# SmartMatrixShield_V1.net
KiCad netlist of a schematic drawn in EAGLE
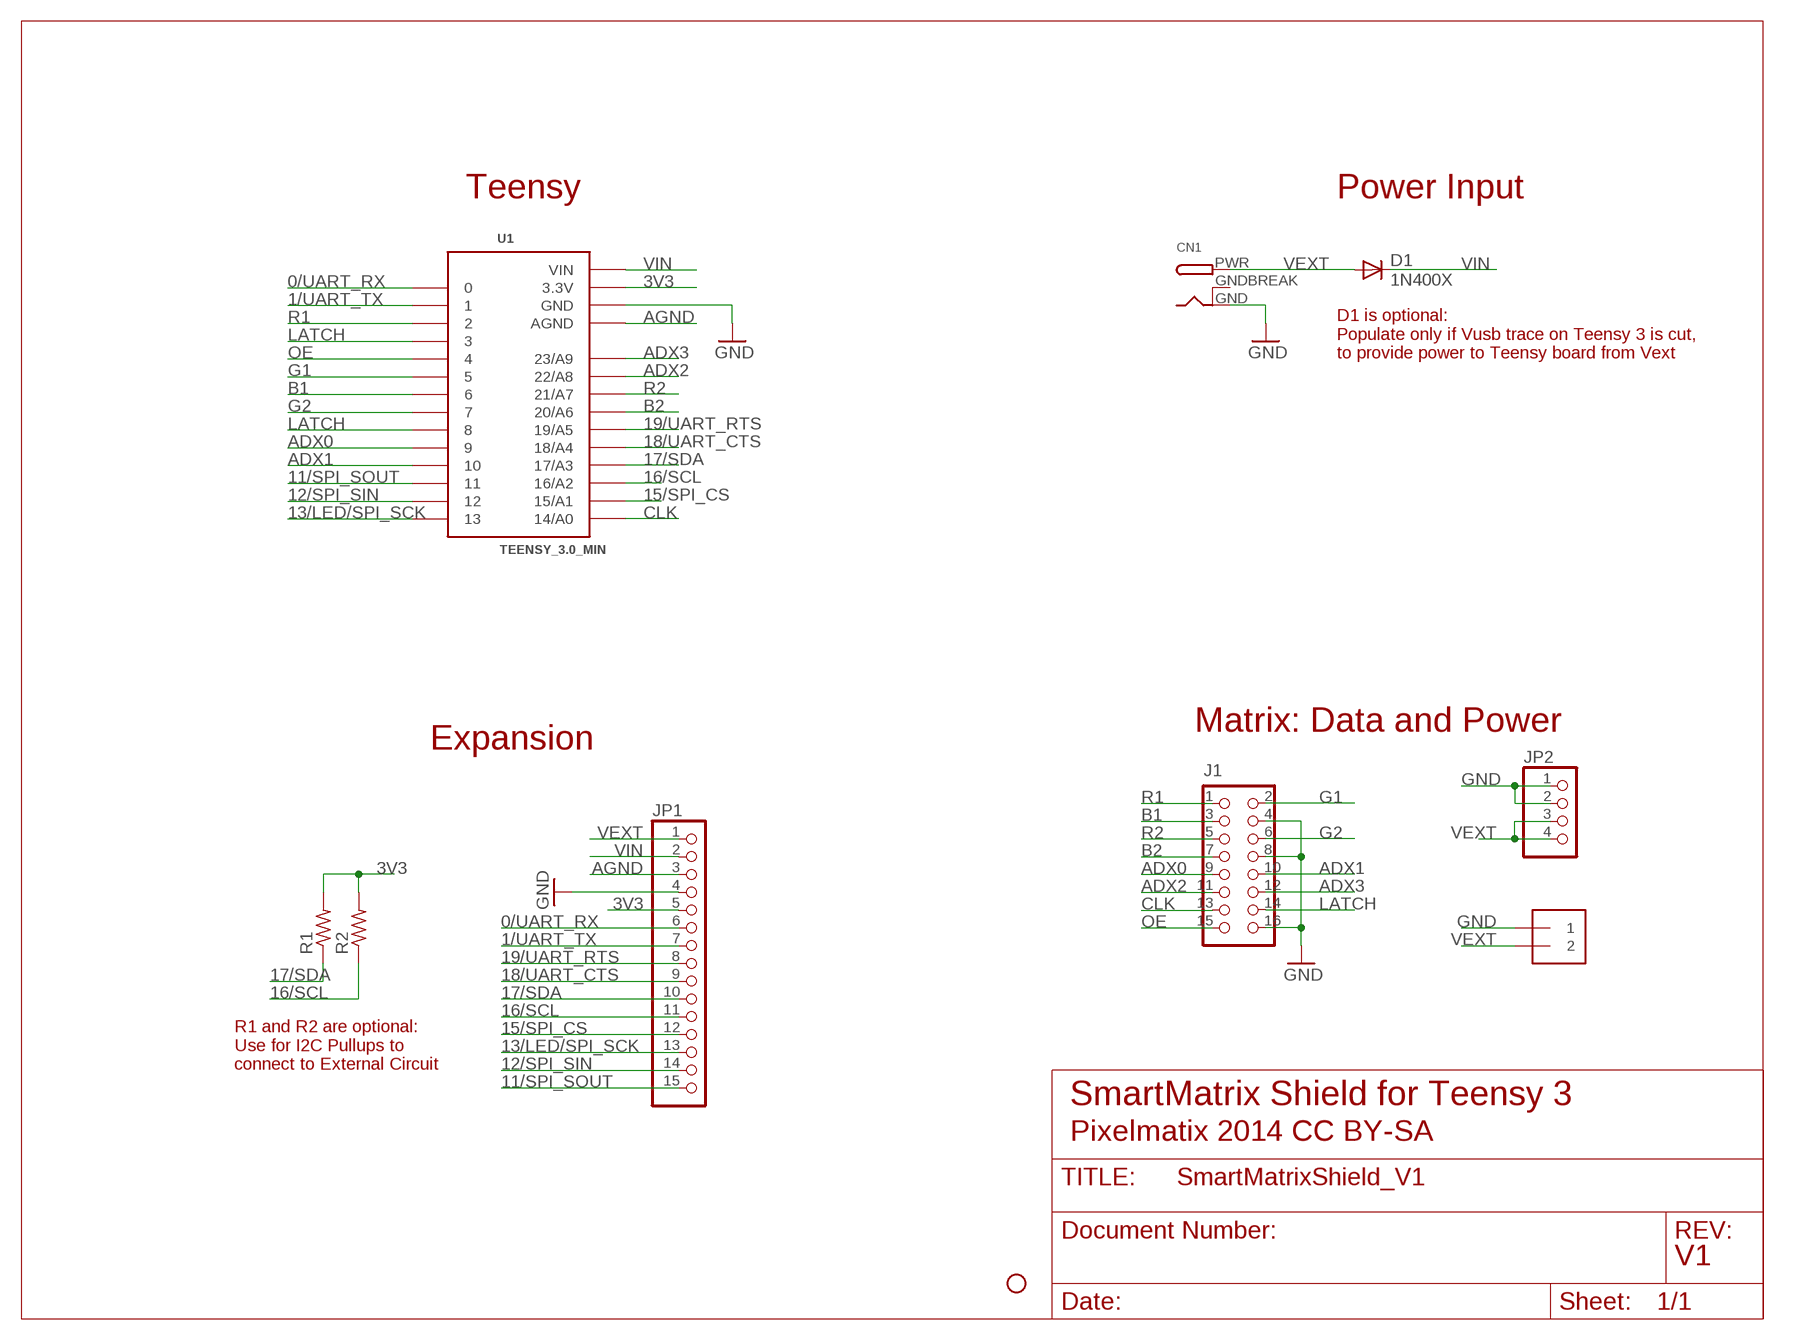
[diagram p0: schematic, sheet 1]

(export (version "E")
  (design (tool "Eeschema 10.0.6"))
  (components
    (comp (ref "CN1")
      (value "DCBARRELPTH")
      (footprint "eagle-import:DCJACK_2MM_PTH")
      (libsource (lib "eagle-import") (part "DCBARRELPTH"))
    )
    (comp (ref "D1")
      (value "1N400X")
      (footprint "eagle-import:DIODE-TH-0.3_")
      (libsource (lib "eagle-import") (part "1N400X"))
    )
    (comp (ref "J1")
      (value "CON_HEADER_2X08-PTH-SHROUDED")
      (footprint "eagle-import:PINSHRD_PTH_2X08")
      (libsource (lib "eagle-import") (part "CON_HEADER_2X08-PTH-SHROUDED"))
    )
    (comp (ref "J4")
      (value "1X2-5.0")
      (footprint "eagle-import:1X2-5.0MM")
      (libsource (lib "eagle-import") (part "1X2-5.0"))
    )
    (comp (ref "JP1")
      (value "PINHD-1X15_2.54-S")
      (footprint "eagle-import:1X15-S")
      (libsource (lib "eagle-import") (part "PINHD-1X15_2.54-S"))
    )
    (comp (ref "JP2")
      (value "PINHD-1X04_1.56")
      (footprint "eagle-import:1X04-1.56_")
      (libsource (lib "eagle-import") (part "PINHD-1X04_1.56"))
    )
    (comp (ref "JP5")
      (value "STAND-OFFSTAND-OFF-3MM")
      (footprint "eagle-import:STAND-OFF-3MM")
      (libsource (lib "eagle-import") (part "STAND-OFFSTAND-OFF-3MM"))
    )
    (comp (ref "R1")
      (value "R-US_0207/7")
      (footprint "eagle-import:0207_7")
      (libsource (lib "eagle-import") (part "R-US_0207/7"))
    )
    (comp (ref "R2")
      (value "R-US_0207/7")
      (footprint "eagle-import:0207_7")
      (libsource (lib "eagle-import") (part "R-US_0207/7"))
    )
    (comp (ref "U1")
      (value "TEENSY_3.0_MIN")
      (footprint "eagle-import:TEENSY_3.0_MIN")
      (libsource (lib "eagle-import") (part "TEENSY_3.0_MIN"))
    )
  )
  (nets
    (net (code "1") (name "/0{slash}UART_RX") (class "Default")
      (node (ref "JP1") (pin "6") (pinfunction "6_6") (pintype "passive"))
      (node (ref "U1") (pin "0") (pinfunction "0_0") (pintype "bidirectional"))
    )
    (net (code "2") (name "/1{slash}UART_TX") (class "Default")
      (node (ref "JP1") (pin "7") (pinfunction "7_7") (pintype "passive"))
      (node (ref "U1") (pin "1") (pinfunction "1_1") (pintype "bidirectional"))
    )
    (net (code "3") (name "/3V3") (class "Default")
      (node (ref "JP1") (pin "5") (pinfunction "5_5") (pintype "passive"))
      (node (ref "R1") (pin "2") (pinfunction "2_2") (pintype "passive"))
      (node (ref "R2") (pin "2") (pinfunction "2_2") (pintype "passive"))
      (node (ref "U1") (pin "3.3V") (pinfunction "3.3V_3.3V") (pintype "power_in"))
    )
    (net (code "4") (name "/11{slash}SPI_SOUT") (class "Default")
      (node (ref "JP1") (pin "15") (pinfunction "15_15") (pintype "passive"))
      (node (ref "U1") (pin "11") (pinfunction "11_11") (pintype "bidirectional"))
    )
    (net (code "5") (name "/12{slash}SPI_SIN") (class "Default")
      (node (ref "JP1") (pin "14") (pinfunction "14_14") (pintype "passive"))
      (node (ref "U1") (pin "12") (pinfunction "12_12") (pintype "bidirectional"))
    )
    (net (code "6") (name "/13{slash}LED{slash}SPI_SCK") (class "Default")
      (node (ref "JP1") (pin "13") (pinfunction "13_13") (pintype "passive"))
      (node (ref "U1") (pin "13") (pinfunction "13_13") (pintype "bidirectional"))
    )
    (net (code "7") (name "/15{slash}SPI_CS") (class "Default")
      (node (ref "JP1") (pin "12") (pinfunction "12_12") (pintype "passive"))
      (node (ref "U1") (pin "15/A1") (pinfunction "15/A1_15/A1") (pintype "bidirectional"))
    )
    (net (code "8") (name "/16{slash}SCL") (class "Default")
      (node (ref "JP1") (pin "11") (pinfunction "11_11") (pintype "passive"))
      (node (ref "R2") (pin "1") (pinfunction "1_1") (pintype "passive"))
      (node (ref "U1") (pin "16/A2") (pinfunction "16/A2_16/A2") (pintype "bidirectional"))
    )
    (net (code "9") (name "/17{slash}SDA") (class "Default")
      (node (ref "JP1") (pin "10") (pinfunction "10_10") (pintype "passive"))
      (node (ref "R1") (pin "1") (pinfunction "1_1") (pintype "passive"))
      (node (ref "U1") (pin "17/A3") (pinfunction "17/A3_17/A3") (pintype "bidirectional"))
    )
    (net (code "10") (name "/18{slash}UART_CTS") (class "Default")
      (node (ref "JP1") (pin "9") (pinfunction "9_9") (pintype "passive"))
      (node (ref "U1") (pin "18/A4") (pinfunction "18/A4_18/A4") (pintype "bidirectional"))
    )
    (net (code "11") (name "/19{slash}UART_RTS") (class "Default")
      (node (ref "JP1") (pin "8") (pinfunction "8_8") (pintype "passive"))
      (node (ref "U1") (pin "19/A5") (pinfunction "19/A5_19/A5") (pintype "bidirectional"))
    )
    (net (code "12") (name "/ADX0") (class "Default")
      (node (ref "J1") (pin "9") (pinfunction "9_9") (pintype "passive"))
      (node (ref "U1") (pin "9") (pinfunction "9_9") (pintype "bidirectional"))
    )
    (net (code "13") (name "/ADX1") (class "Default")
      (node (ref "J1") (pin "10") (pinfunction "10_10") (pintype "passive"))
      (node (ref "U1") (pin "10") (pinfunction "10_10") (pintype "bidirectional"))
    )
    (net (code "14") (name "/ADX2") (class "Default")
      (node (ref "J1") (pin "11") (pinfunction "11_11") (pintype "passive"))
      (node (ref "U1") (pin "22/A8") (pinfunction "22/A8_22/A8") (pintype "bidirectional"))
    )
    (net (code "15") (name "/ADX3") (class "Default")
      (node (ref "J1") (pin "12") (pinfunction "12_12") (pintype "passive"))
      (node (ref "U1") (pin "23/A9") (pinfunction "23/A9_23/A9") (pintype "bidirectional"))
    )
    (net (code "16") (name "/AGND") (class "Default")
      (node (ref "JP1") (pin "3") (pinfunction "3_3") (pintype "passive"))
      (node (ref "U1") (pin "AGND") (pinfunction "AGND_AGND") (pintype "power_in"))
    )
    (net (code "17") (name "/B1") (class "Default")
      (node (ref "J1") (pin "3") (pinfunction "3_3") (pintype "passive"))
      (node (ref "U1") (pin "6") (pinfunction "6_6") (pintype "bidirectional"))
    )
    (net (code "18") (name "/B2") (class "Default")
      (node (ref "J1") (pin "7") (pinfunction "7_7") (pintype "passive"))
      (node (ref "U1") (pin "20/A6") (pinfunction "20/A6_20/A6") (pintype "bidirectional"))
    )
    (net (code "19") (name "/CLK") (class "Default")
      (node (ref "J1") (pin "13") (pinfunction "13_13") (pintype "passive"))
      (node (ref "U1") (pin "14/A0") (pinfunction "14/A0_14/A0") (pintype "bidirectional"))
    )
    (net (code "20") (name "/G1") (class "Default")
      (node (ref "J1") (pin "2") (pinfunction "2_2") (pintype "passive"))
      (node (ref "U1") (pin "5") (pinfunction "5_5") (pintype "bidirectional"))
    )
    (net (code "21") (name "/G2") (class "Default")
      (node (ref "J1") (pin "6") (pinfunction "6_6") (pintype "passive"))
      (node (ref "U1") (pin "7") (pinfunction "7_7") (pintype "bidirectional"))
    )
    (net (code "22") (name "/GNDBREAK") (class "Default")
      (node (ref "CN1") (pin "GNDBREAK") (pinfunction "GNDBREAK_GNDBREAK") (pintype "power_in"))
    )
    (net (code "23") (name "/LATCH") (class "Default")
      (node (ref "J1") (pin "14") (pinfunction "14_14") (pintype "passive"))
      (node (ref "U1") (pin "3") (pinfunction "3_3") (pintype "bidirectional"))
      (node (ref "U1") (pin "8") (pinfunction "8_8") (pintype "bidirectional"))
    )
    (net (code "24") (name "/OE") (class "Default")
      (node (ref "J1") (pin "15") (pinfunction "15_15") (pintype "passive"))
      (node (ref "U1") (pin "4") (pinfunction "4_4") (pintype "bidirectional"))
    )
    (net (code "25") (name "/R1") (class "Default")
      (node (ref "J1") (pin "1") (pinfunction "1_1") (pintype "passive"))
      (node (ref "U1") (pin "2") (pinfunction "2_2") (pintype "bidirectional"))
    )
    (net (code "26") (name "/R2") (class "Default")
      (node (ref "J1") (pin "5") (pinfunction "5_5") (pintype "passive"))
      (node (ref "U1") (pin "21/A7") (pinfunction "21/A7_21/A7") (pintype "bidirectional"))
    )
    (net (code "27") (name "/VEXT") (class "Default")
      (node (ref "CN1") (pin "PWR") (pinfunction "PWR_PWR") (pintype "power_in"))
      (node (ref "D1") (pin "A") (pinfunction "A_A") (pintype "passive"))
      (node (ref "J4") (pin "2") (pinfunction "2_2") (pintype "passive"))
      (node (ref "JP1") (pin "1") (pinfunction "1_1") (pintype "passive"))
      (node (ref "JP2") (pin "3") (pinfunction "3_3") (pintype "passive"))
      (node (ref "JP2") (pin "4") (pinfunction "4_4") (pintype "passive"))
    )
    (net (code "28") (name "/VIN") (class "Default")
      (node (ref "D1") (pin "C") (pinfunction "C_C") (pintype "passive"))
      (node (ref "JP1") (pin "2") (pinfunction "2_2") (pintype "passive"))
      (node (ref "U1") (pin "VIN") (pinfunction "VIN_VIN") (pintype "power_in"))
    )
    (net (code "29") (name "GND") (class "Default")
      (node (ref "CN1") (pin "GND") (pinfunction "GND_GND") (pintype "power_in"))
      (node (ref "J1") (pin "16") (pinfunction "16_16") (pintype "passive"))
      (node (ref "J1") (pin "4") (pinfunction "4_4") (pintype "passive"))
      (node (ref "J1") (pin "8") (pinfunction "8_8") (pintype "passive"))
      (node (ref "J4") (pin "1") (pinfunction "1_1") (pintype "passive"))
      (node (ref "JP1") (pin "4") (pinfunction "4_4") (pintype "passive"))
      (node (ref "JP2") (pin "1") (pinfunction "1_1") (pintype "passive"))
      (node (ref "JP2") (pin "2") (pinfunction "2_2") (pintype "passive"))
      (node (ref "U1") (pin "GND") (pinfunction "GND_GND") (pintype "power_in"))
    )
  )
)
